# Driver.net
KiCad netlist of a schematic drawn in Altium Designer
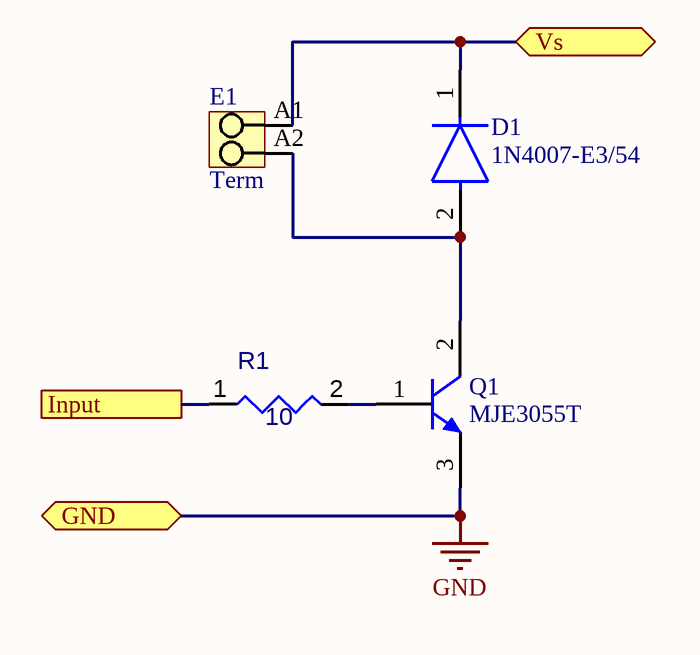
[diagram p0: Driver.SchDoc]

(export (version "E")
  (design (tool "Eeschema 10.0.6"))
  (components
    (comp (ref "D1")
      (value "1N4007-E3/54")
      (footprint "FP-1N4007-MFG")
      (description "DIODE GEN PURP 1KV 1A DO204AL")
      (fields
        (field (name "OCTOPART") "https://octopart.com/1n4007-e3%2F54-vishay-39548207")
        (field (name "MANUFACTURER") "Vishay")
      )
      (libsource (lib "Altium Content Vault") (part "d7152d700b627762746794eb795d46e"))
    )
    (comp (ref "E1")
      (value "Term")
      (footprint "PM_5_08_90_02")
      (description "OMNIMATE Signal - series PM")
      (fields (field (name "MANUFACTURER") "Weidmueller") (field (name "PARTNUMBER") "1760490000"))
      (libsource (lib "Altium Content Vault") (part "Terminal_02_1x02"))
    )
    (comp (ref "Q1")
      (value "MJE3055T")
      (footprint "ONSC-TO-220-3-221A-09")
      (description "Complementary Silicon Plastic Power Transistor, 3-Pin TO-220, Tube")
      (fields (field (name "MANUFACTURER") "On Semiconductor"))
      (libsource (lib "Altium Content Vault") (part "ONSC-NPN-B1C2E3-3_C"))
    )
    (comp (ref "R1")
      (value "10")
      (footprint "RESA60-630X240")
      (description "Axial, 10ohm, 0.5W")
      (fields (field (name "MANUFACTURER") "Yageo") (field (name "POWER") "250mW"))
      (libsource (lib "National Institutes of Health-IDEAS") (part "RES-2"))
    )
  )
  (nets
    (net (code "1") (name "/Input") (class "Default")
      (node (ref "R1") (pin "1") (pinfunction "1_1") (pintype "passive"))
    )
    (net (code "2") (name "/Vs") (class "Default")
      (node (ref "D1") (pin "1") (pinfunction "C_1") (pintype "passive"))
      (node (ref "E1") (pin "A1") (pinfunction "A1_A1") (pintype "passive"))
    )
    (net (code "3") (name "GND") (class "Default")
      (node (ref "Q1") (pin "3") (pinfunction "E_3") (pintype "passive"))
    )
    (net (code "4") (name "Net-(D1-A)") (class "Default")
      (node (ref "D1") (pin "2") (pinfunction "A_2") (pintype "passive"))
      (node (ref "E1") (pin "A2") (pinfunction "A2_A2") (pintype "passive"))
      (node (ref "Q1") (pin "2") (pinfunction "C_2") (pintype "passive"))
    )
    (net (code "5") (name "Net-(Q1-B)") (class "Default")
      (node (ref "Q1") (pin "1") (pinfunction "B_1") (pintype "passive"))
      (node (ref "R1") (pin "2") (pinfunction "2_2") (pintype "passive"))
    )
  )
)
